# SX1262_e428v03a.net
KiCad netlist of a schematic drawn in Altium Designer
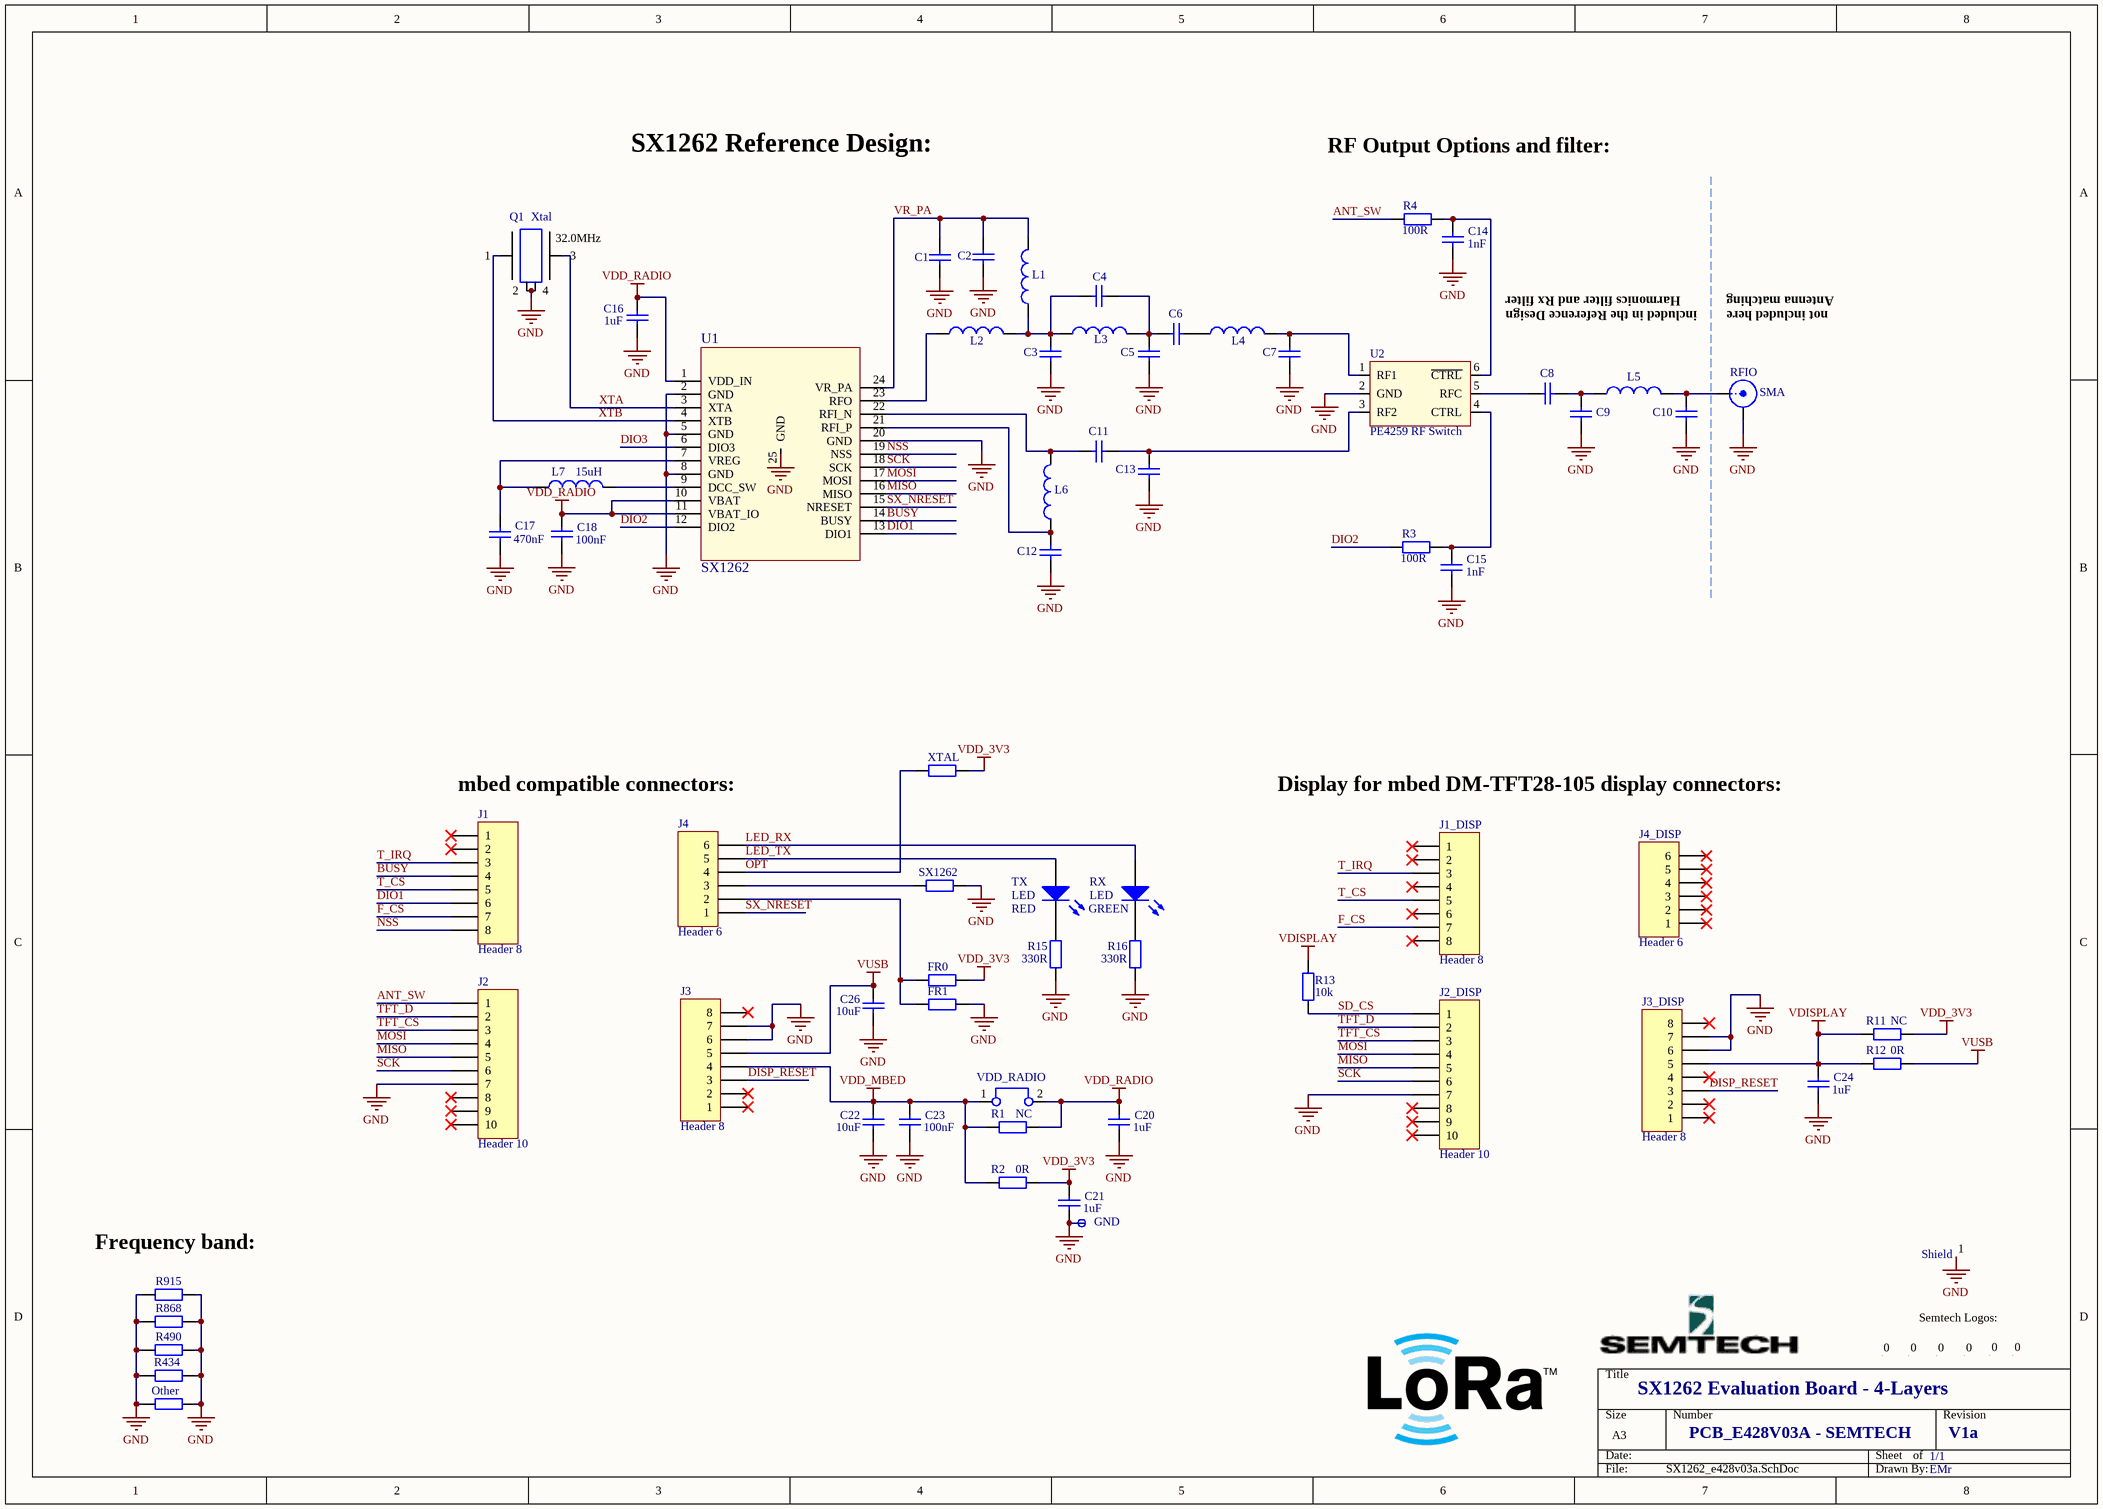
[diagram p0: SX1262_e428v03a.SchDoc]

(export (version "E")
  (design (tool "Eeschema 10.0.6"))
  (components
    (comp (ref "C1")
      (value "Cap")
      (footprint "rlc_402_smd")
      (description "Capacitor SMD")
      (fields (field (name "PUBLISHER") "Altium Limited"))
      (libsource (lib "SX1262_e428v03a") (part "Cap"))
    )
    (comp (ref "C2")
      (value "Cap")
      (footprint "rlc_402_smd")
      (description "Capacitor SMD")
      (fields (field (name "PUBLISHER") "Altium Limited"))
      (libsource (lib "SX1262_e428v03a") (part "Cap"))
    )
    (comp (ref "C3")
      (value "Cap")
      (footprint "rlc_402_smd")
      (description "Capacitor SMD")
      (fields (field (name "PUBLISHER") "Altium Limited"))
      (libsource (lib "SX1262_e428v03a") (part "Cap"))
    )
    (comp (ref "C4")
      (value "Cap")
      (footprint "rlc_402_smd")
      (description "Capacitor SMD")
      (fields (field (name "PUBLISHER") "Altium Limited"))
      (libsource (lib "SX1262_e428v03a") (part "Cap"))
    )
    (comp (ref "C5")
      (value "Cap")
      (footprint "rlc_402_smd")
      (description "Capacitor SMD")
      (fields (field (name "PUBLISHER") "Altium Limited"))
      (libsource (lib "SX1262_e428v03a") (part "Cap"))
    )
    (comp (ref "C6")
      (value "Cap")
      (footprint "rlc_402_smd")
      (description "Capacitor SMD")
      (fields (field (name "PUBLISHER") "Altium Limited"))
      (libsource (lib "SX1262_e428v03a") (part "Cap"))
    )
    (comp (ref "C7")
      (value "Cap")
      (footprint "rlc_402_smd")
      (description "Capacitor SMD")
      (fields (field (name "PUBLISHER") "Altium Limited"))
      (libsource (lib "SX1262_e428v03a") (part "Cap"))
    )
    (comp (ref "C8")
      (value "Cap")
      (footprint "rlc_402_smd")
      (description "Capacitor SMD")
      (fields (field (name "PUBLISHER") "Altium Limited"))
      (libsource (lib "SX1262_e428v03a") (part "Cap"))
    )
    (comp (ref "C9")
      (value "Cap")
      (footprint "rlc_402_smd")
      (description "Capacitor SMD")
      (fields (field (name "PUBLISHER") "Altium Limited"))
      (libsource (lib "SX1262_e428v03a") (part "Cap"))
    )
    (comp (ref "C10")
      (value "Cap")
      (footprint "rlc_402_smd")
      (description "Capacitor SMD")
      (fields (field (name "PUBLISHER") "Altium Limited"))
      (libsource (lib "SX1262_e428v03a") (part "Cap"))
    )
    (comp (ref "C11")
      (value "Cap")
      (footprint "rlc_402_smd")
      (description "Capacitor SMD")
      (fields (field (name "PUBLISHER") "Altium Limited"))
      (libsource (lib "SX1262_e428v03a") (part "Cap"))
    )
    (comp (ref "C12")
      (value "Cap")
      (footprint "rlc_402_smd")
      (description "Capacitor SMD")
      (fields (field (name "PUBLISHER") "Altium Limited"))
      (libsource (lib "SX1262_e428v03a") (part "Cap"))
    )
    (comp (ref "C13")
      (value "Cap")
      (footprint "rlc_402_smd")
      (description "Capacitor SMD")
      (fields (field (name "PUBLISHER") "Altium Limited"))
      (libsource (lib "SX1262_e428v03a") (part "Cap"))
    )
    (comp (ref "C14")
      (value "1nF")
      (footprint "rlc_402_smd")
      (description "Capacitor SMD")
      (fields (field (name "Comment") "Cap") (field (name "PUBLISHER") "Altium Limited"))
      (libsource (lib "SX1262_e428v03a") (part "Cap"))
    )
    (comp (ref "C15")
      (value "1nF")
      (footprint "rlc_402_smd")
      (description "Capacitor SMD")
      (fields (field (name "Comment") "Cap") (field (name "PUBLISHER") "Altium Limited"))
      (libsource (lib "SX1262_e428v03a") (part "Cap"))
    )
    (comp (ref "C16")
      (value "1uF")
      (footprint "rlc_402_smd")
      (description "Capacitor SMD")
      (fields (field (name "Comment") "Cap") (field (name "PUBLISHER") "Altium Limited"))
      (libsource (lib "SX1262_e428v03a") (part "Cap"))
    )
    (comp (ref "C17")
      (value "470nF")
      (footprint "rlc_402_smd")
      (description "Capacitor SMD")
      (fields (field (name "Comment") "Cap") (field (name "PUBLISHER") "Altium Limited"))
      (libsource (lib "SX1262_e428v03a") (part "Cap"))
    )
    (comp (ref "C18")
      (value "100nF")
      (footprint "rlc_402_smd")
      (description "Capacitor SMD")
      (fields (field (name "Comment") "Cap") (field (name "PUBLISHER") "Altium Limited"))
      (libsource (lib "SX1262_e428v03a") (part "Cap"))
    )
    (comp (ref "C20")
      (value "1uF")
      (footprint "rlc_603_smd")
      (description "Capacitor SMD")
      (fields (field (name "Comment") "Cap") (field (name "PUBLISHER") "Altium Limited"))
      (libsource (lib "SX1262_e428v03a") (part "Cap"))
    )
    (comp (ref "C21")
      (value "1uF")
      (footprint "rlc_603_smd")
      (description "Capacitor SMD")
      (fields (field (name "Comment") "Cap") (field (name "PUBLISHER") "Altium Limited"))
      (libsource (lib "SX1262_e428v03a") (part "Cap"))
    )
    (comp (ref "C22")
      (value "10uF")
      (footprint "rlc_805_smd")
      (description "Capacitor SMD")
      (fields (field (name "Comment") "Cap") (field (name "PUBLISHER") "Altium Limited"))
      (libsource (lib "SX1262_e428v03a") (part "Cap"))
    )
    (comp (ref "C23")
      (value "100nF")
      (footprint "rlc_402_smd")
      (description "Capacitor SMD")
      (fields (field (name "Comment") "Cap") (field (name "PUBLISHER") "Altium Limited"))
      (libsource (lib "SX1262_e428v03a") (part "Cap"))
    )
    (comp (ref "C24")
      (value "1uF")
      (footprint "rlc_402_smd")
      (description "Capacitor SMD")
      (fields (field (name "Comment") "Cap") (field (name "PUBLISHER") "Altium Limited"))
      (libsource (lib "SX1262_e428v03a") (part "Cap"))
    )
    (comp (ref "C26")
      (value "10uF")
      (footprint "rlc_805_smd")
      (description "Capacitor SMD")
      (fields (field (name "Comment") "Cap") (field (name "PUBLISHER") "Altium Limited"))
      (libsource (lib "SX1262_e428v03a") (part "Cap"))
    )
    (comp (ref "FR0")
      (value "Resistor")
      (footprint "rlc_402_smd")
      (description "Resistor SMD - IEC symbol version")
      (libsource (lib "") (part "Resistor_1"))
    )
    (comp (ref "FR1")
      (value "Resistor")
      (footprint "rlc_402_smd")
      (description "Resistor SMD - IEC symbol version")
      (libsource (lib "") (part "Resistor_1"))
    )
    (comp (ref "GND")
      (value "Test Pin")
      (footprint "pin_0.9mm")
      (libsource (lib "SX1262_e428v03a") (part "test_pin"))
    )
    (comp (ref "J1")
      (value "Header 8")
      (footprint "HDR1X8")
      (description "Header, 8-Pin")
      (fields (field (name "PUBLISHER") "Altium Limited"))
      (libsource (lib "SX1262_e428v03a") (part "Header 8"))
    )
    (comp (ref "J1_DISP")
      (value "Header 8")
      (footprint "HDR1X8")
      (description "Header, 8-Pin")
      (fields (field (name "PUBLISHER") "Altium Limited"))
      (libsource (lib "SX1262_e428v03a") (part "Header 8"))
    )
    (comp (ref "J2")
      (value "Header 10")
      (footprint "HDR1X10")
      (description "Header, 10-Pin")
      (fields (field (name "PUBLISHER") "Altium Limited"))
      (libsource (lib "SX1262_e428v03a") (part "Header 10"))
    )
    (comp (ref "J2_DISP")
      (value "Header 10")
      (footprint "HDR1X10")
      (description "Header, 10-Pin")
      (fields (field (name "PUBLISHER") "Altium Limited"))
      (libsource (lib "SX1262_e428v03a") (part "Header 10"))
    )
    (comp (ref "J3")
      (value "Header 8")
      (footprint "HDR1X8")
      (description "Header, 8-Pin")
      (fields (field (name "PUBLISHER") "Altium Limited"))
      (libsource (lib "") (part "Header 8_1"))
    )
    (comp (ref "J3_DISP")
      (value "Header 8")
      (footprint "HDR1X8")
      (description "Header, 8-Pin")
      (fields (field (name "PUBLISHER") "Altium Limited"))
      (libsource (lib "") (part "Header 8_1"))
    )
    (comp (ref "J4")
      (value "Header 6")
      (footprint "HDR1X6")
      (description "Header, 6-Pin")
      (fields (field (name "PUBLISHER") "Altium Limited"))
      (libsource (lib "SX1262_e428v03a") (part "Header 6"))
    )
    (comp (ref "J4_DISP")
      (value "Header 6")
      (footprint "HDR1X6")
      (description "Header, 6-Pin")
      (fields (field (name "PUBLISHER") "Altium Limited"))
      (libsource (lib "SX1262_e428v03a") (part "Header 6"))
    )
    (comp (ref "L1")
      (value "Inductor")
      (footprint "rlc_402_smd")
      (description "Inductor SMD")
      (fields (field (name "PUBLISHER") "Altium Limited"))
      (libsource (lib "SX1262_e428v03a") (part "Inductor"))
    )
    (comp (ref "L2")
      (value "Inductor")
      (footprint "rlc_402_smd")
      (description "Inductor SMD")
      (fields (field (name "PUBLISHER") "Altium Limited"))
      (libsource (lib "SX1262_e428v03a") (part "Inductor"))
    )
    (comp (ref "L3")
      (value "Inductor")
      (footprint "rlc_402_smd")
      (description "Inductor SMD")
      (fields (field (name "PUBLISHER") "Altium Limited"))
      (libsource (lib "SX1262_e428v03a") (part "Inductor"))
    )
    (comp (ref "L4")
      (value "Inductor")
      (footprint "rlc_402_smd")
      (description "Inductor SMD")
      (fields (field (name "PUBLISHER") "Altium Limited"))
      (libsource (lib "SX1262_e428v03a") (part "Inductor"))
    )
    (comp (ref "L5")
      (value "Inductor")
      (footprint "rlc_402_smd")
      (description "Inductor SMD")
      (fields (field (name "PUBLISHER") "Altium Limited"))
      (libsource (lib "SX1262_e428v03a") (part "Inductor"))
    )
    (comp (ref "L6")
      (value "Inductor")
      (footprint "rlc_402_smd")
      (description "Inductor SMD")
      (fields (field (name "PUBLISHER") "Altium Limited"))
      (libsource (lib "SX1262_e428v03a") (part "Inductor"))
    )
    (comp (ref "L7")
      (value "15uH")
      (footprint "rlc_805_smd enlarged")
      (description "Inductor SMD")
      (fields (field (name "Comment") "Inductor") (field (name "PUBLISHER") "Altium Limited"))
      (libsource (lib "SX1262_e428v03a") (part "Inductor"))
    )
    (comp (ref "Logo Bot")
      (value "Logo symbol")
      (footprint "logo_semtech_horiz_size4")
      (description "Schematic symbol for Logo")
      (libsource (lib "SX1262_e428v03a") (part "Logo"))
    )
    (comp (ref "Logo ESD")
      (value "Logo symbol")
      (footprint "Logo ESD")
      (description "Schematic symbol for Logo")
      (libsource (lib "SX1262_e428v03a") (part "Logo"))
    )
    (comp (ref "Logo Recycling1")
      (value "Logo symbol")
      (footprint "Logo Recycling1")
      (description "Schematic symbol for Logo")
      (libsource (lib "SX1262_e428v03a") (part "Logo"))
    )
    (comp (ref "Logo Semtech S")
      (value "Logo symbol")
      (footprint "logo_semtech_horiz_size3")
      (description "Schematic symbol for Logo")
      (libsource (lib "SX1262_e428v03a") (part "Logo"))
    )
    (comp (ref "Logo_LoRA1")
      (value "Logo symbol")
      (footprint "Logo LoRa Size4")
      (description "Schematic symbol for Logo")
      (libsource (lib "SX1262_e428v03a") (part "Logo"))
    )
    (comp (ref "Logo_LoRA2")
      (value "Logo symbol")
      (footprint "Logo LoRa Size3")
      (description "Schematic symbol for Logo")
      (libsource (lib "SX1262_e428v03a") (part "Logo"))
    )
    (comp (ref "Other")
      (value "Resistor")
      (footprint "rlc_402_smd")
      (description "Resistor SMD - IEC symbol version")
      (libsource (lib "SX1262_e428v03a") (part "Resistor"))
    )
    (comp (ref "Q1")
      (value "Xtal")
      (footprint "nd2016da")
      (description "Crystal with GND pins")
      (fields (field (name "ALTIUM_VALUE") "32.0MHz"))
      (libsource (lib "SX1262_e428v03a") (part "Xtal GND"))
    )
    (comp (ref "R1")
      (value "NC")
      (footprint "rlc_603_smd")
      (description "Resistor SMD - IEC symbol version")
      (fields (field (name "Comment") "Resistor"))
      (libsource (lib "SX1262_e428v03a") (part "Resistor"))
    )
    (comp (ref "R2")
      (value "0R")
      (footprint "rlc_603_smd")
      (description "Resistor SMD - IEC symbol version")
      (fields (field (name "Comment") "Resistor"))
      (libsource (lib "SX1262_e428v03a") (part "Resistor"))
    )
    (comp (ref "R3")
      (value "100R")
      (footprint "rlc_402_smd")
      (description "Resistor SMD - IEC symbol version")
      (fields (field (name "Comment") "Resistor"))
      (libsource (lib "SX1262_e428v03a") (part "Resistor"))
    )
    (comp (ref "R4")
      (value "100R")
      (footprint "rlc_402_smd")
      (description "Resistor SMD - IEC symbol version")
      (fields (field (name "Comment") "Resistor"))
      (libsource (lib "SX1262_e428v03a") (part "Resistor"))
    )
    (comp (ref "R11")
      (value "NC")
      (footprint "rlc_402_smd")
      (description "Resistor SMD - IEC symbol version")
      (fields (field (name "Comment") "Resistor"))
      (libsource (lib "SX1262_e428v03a") (part "Resistor"))
    )
    (comp (ref "R12")
      (value "0R")
      (footprint "rlc_402_smd")
      (description "Resistor SMD - IEC symbol version")
      (fields (field (name "Comment") "Resistor"))
      (libsource (lib "SX1262_e428v03a") (part "Resistor"))
    )
    (comp (ref "R13")
      (value "10k")
      (footprint "rlc_402_smd")
      (description "Resistor SMD - IEC symbol version")
      (fields (field (name "Comment") "Resistor"))
      (libsource (lib "SX1262_e428v03a") (part "Resistor"))
    )
    (comp (ref "R15")
      (value "330R")
      (footprint "rlc_402_smd")
      (description "Resistor SMD - IEC symbol version")
      (fields (field (name "Comment") "Resistor"))
      (libsource (lib "") (part "Resistor_2"))
    )
    (comp (ref "R16")
      (value "330R")
      (footprint "rlc_402_smd")
      (description "Resistor SMD - IEC symbol version")
      (fields (field (name "Comment") "Resistor"))
      (libsource (lib "") (part "Resistor_2"))
    )
    (comp (ref "R434")
      (value "Resistor")
      (footprint "rlc_402_smd")
      (description "Resistor SMD - IEC symbol version")
      (libsource (lib "SX1262_e428v03a") (part "Resistor"))
    )
    (comp (ref "R490")
      (value "Resistor")
      (footprint "rlc_402_smd")
      (description "Resistor SMD - IEC symbol version")
      (libsource (lib "SX1262_e428v03a") (part "Resistor"))
    )
    (comp (ref "R868")
      (value "Resistor")
      (footprint "rlc_402_smd")
      (description "Resistor SMD - IEC symbol version")
      (libsource (lib "SX1262_e428v03a") (part "Resistor"))
    )
    (comp (ref "R915")
      (value "Resistor")
      (footprint "rlc_402_smd")
      (description "Resistor SMD - IEC symbol version")
      (libsource (lib "SX1262_e428v03a") (part "Resistor"))
    )
    (comp (ref "RFIO")
      (value "SMA")
      (footprint "SMA_end_launch_1.0mm_9.52mm")
      (description "SMA Straight Connector")
      (fields (field (name "PUBLISHER") "Altium Limited"))
      (libsource (lib "SX1262_e428v03a") (part "SMA"))
    )
    (comp (ref "RX")
      (value "LED")
      (footprint "LGM676 LED")
      (fields (field (name "ALTIUM_VALUE") "GREEN"))
      (libsource (lib "SX1262_e428v03a") (part "LED"))
    )
    (comp (ref "Shield")
      (value "Logo symbol")
      (footprint "BMIS-209-F - Shield - Solder_Mask")
      (description "Shield - EMI Gasket - Standard Surface Mount Shields")
      (libsource (lib "SX1262_e428v03a") (part "Shield"))
    )
    (comp (ref "SX1262")
      (value "Resistor")
      (footprint "rlc_402_smd")
      (description "Resistor SMD - IEC symbol version")
      (libsource (lib "") (part "Resistor_1"))
    )
    (comp (ref "TX")
      (value "LED")
      (footprint "LGM676 LED")
      (fields (field (name "ALTIUM_VALUE") "RED"))
      (libsource (lib "SX1262_e428v03a") (part "LED"))
    )
    (comp (ref "U1")
      (value "SX1262")
      (footprint "vqfn24_4x4mm")
      (description "SX1262- Ultra low power RF transceiver")
      (libsource (lib "SX1262_e428v03a") (part "SX126x"))
    )
    (comp (ref "U2")
      (value "PE4259 RF Switch")
      (footprint "SC70-6")
      (description "PE4259 Peregrine RF Switch")
      (libsource (lib "SX1262_e428v03a") (part "PE4259 RF Switch"))
    )
    (comp (ref "VDD_RADIO")
      (value "Jumper")
      (footprint "bridge_254mm")
      (description "Jumper Wire")
      (libsource (lib "SX1262_e428v03a") (part "Jumper"))
    )
    (comp (ref "XTAL")
      (value "Resistor")
      (footprint "rlc_402_smd")
      (description "Resistor SMD - IEC symbol version")
      (libsource (lib "") (part "Resistor_1"))
    )
  )
  (nets
    (net (code "1") (name "/ANT_SW") (class "Default")
      (node (ref "J2") (pin "1") (pinfunction "1_1") (pintype "passive"))
      (node (ref "R4") (pin "2") (pinfunction "2_2") (pintype "passive"))
    )
    (net (code "2") (name "/BUSY") (class "Default")
      (node (ref "J1") (pin "4") (pinfunction "4_4") (pintype "passive"))
      (node (ref "U1") (pin "14") (pinfunction "BUSY_14") (pintype "passive"))
    )
    (net (code "3") (name "/DIO1") (class "Default")
      (node (ref "J1") (pin "6") (pinfunction "6_6") (pintype "passive"))
      (node (ref "U1") (pin "13") (pinfunction "DIO1_13") (pintype "passive"))
    )
    (net (code "4") (name "/DIO2") (class "Default")
      (node (ref "R3") (pin "2") (pinfunction "2_2") (pintype "passive"))
      (node (ref "U1") (pin "12") (pinfunction "DIO2_12") (pintype "passive"))
    )
    (net (code "5") (name "/DIO3") (class "Default")
      (node (ref "U1") (pin "6") (pinfunction "DIO3_6") (pintype "passive"))
    )
    (net (code "6") (name "/DISP_RESET") (class "Default")
      (node (ref "J3") (pin "3") (pinfunction "3_3") (pintype "passive"))
      (node (ref "J3_DISP") (pin "3") (pinfunction "3_3") (pintype "passive"))
    )
    (net (code "7") (name "/F_CS") (class "Default")
      (node (ref "J1") (pin "7") (pinfunction "7_7") (pintype "passive"))
      (node (ref "J1_DISP") (pin "7") (pinfunction "7_7") (pintype "passive"))
    )
    (net (code "8") (name "/LED_RX") (class "Default")
      (node (ref "J4") (pin "6") (pinfunction "6_6") (pintype "passive"))
      (node (ref "RX") (pin "1") (pinfunction "A_1") (pintype "passive"))
    )
    (net (code "9") (name "/LED_TX") (class "Default")
      (node (ref "J4") (pin "5") (pinfunction "5_5") (pintype "passive"))
      (node (ref "TX") (pin "1") (pinfunction "A_1") (pintype "passive"))
    )
    (net (code "10") (name "/MISO") (class "Default")
      (node (ref "J2") (pin "5") (pinfunction "5_5") (pintype "passive"))
      (node (ref "J2_DISP") (pin "5") (pinfunction "5_5") (pintype "passive"))
      (node (ref "U1") (pin "16") (pinfunction "MISO_16") (pintype "passive"))
    )
    (net (code "11") (name "/MOSI") (class "Default")
      (node (ref "J2") (pin "4") (pinfunction "4_4") (pintype "passive"))
      (node (ref "J2_DISP") (pin "4") (pinfunction "4_4") (pintype "passive"))
      (node (ref "U1") (pin "17") (pinfunction "MOSI_17") (pintype "passive"))
    )
    (net (code "12") (name "/NSS") (class "Default")
      (node (ref "J1") (pin "8") (pinfunction "8_8") (pintype "passive"))
      (node (ref "U1") (pin "19") (pinfunction "NSS_19") (pintype "passive"))
    )
    (net (code "13") (name "/OPT") (class "Default")
      (node (ref "J4") (pin "4") (pinfunction "4_4") (pintype "passive"))
      (node (ref "XTAL") (pin "2") (pinfunction "2_2") (pintype "passive"))
    )
    (net (code "14") (name "/SCK") (class "Default")
      (node (ref "J2") (pin "6") (pinfunction "6_6") (pintype "passive"))
      (node (ref "J2_DISP") (pin "6") (pinfunction "6_6") (pintype "passive"))
      (node (ref "U1") (pin "18") (pinfunction "SCK_18") (pintype "passive"))
    )
    (net (code "15") (name "/SD_CS") (class "Default")
      (node (ref "J2_DISP") (pin "1") (pinfunction "1_1") (pintype "passive"))
      (node (ref "R13") (pin "2") (pinfunction "2_2") (pintype "passive"))
    )
    (net (code "16") (name "/SX_NRESET") (class "Default")
      (node (ref "J4") (pin "1") (pinfunction "1_1") (pintype "passive"))
      (node (ref "U1") (pin "15") (pinfunction "NRESET_15") (pintype "passive"))
    )
    (net (code "17") (name "/TFT_CS") (class "Default")
      (node (ref "J2") (pin "3") (pinfunction "3_3") (pintype "passive"))
      (node (ref "J2_DISP") (pin "3") (pinfunction "3_3") (pintype "passive"))
    )
    (net (code "18") (name "/TFT_D") (class "Default")
      (node (ref "J2") (pin "2") (pinfunction "2_2") (pintype "passive"))
      (node (ref "J2_DISP") (pin "2") (pinfunction "2_2") (pintype "passive"))
    )
    (net (code "19") (name "/T_CS") (class "Default")
      (node (ref "J1") (pin "5") (pinfunction "5_5") (pintype "passive"))
      (node (ref "J1_DISP") (pin "5") (pinfunction "5_5") (pintype "passive"))
    )
    (net (code "20") (name "/T_IRQ") (class "Default")
      (node (ref "J1") (pin "3") (pinfunction "3_3") (pintype "passive"))
      (node (ref "J1_DISP") (pin "3") (pinfunction "3_3") (pintype "passive"))
    )
    (net (code "21") (name "/VR_PA") (class "Default")
      (node (ref "C1") (pin "2") (pinfunction "2_2") (pintype "passive"))
      (node (ref "C2") (pin "2") (pinfunction "2_2") (pintype "passive"))
      (node (ref "L1") (pin "2") (pinfunction "2_2") (pintype "passive"))
      (node (ref "U1") (pin "24") (pinfunction "VR_PA_24") (pintype "power_in"))
    )
    (net (code "22") (name "/XTA") (class "Default")
      (node (ref "Q1") (pin "3") (pinfunction "3_3") (pintype "passive"))
      (node (ref "U1") (pin "3") (pinfunction "XTA_3") (pintype "passive"))
    )
    (net (code "24") (name "/XTB") (class "Default")
      (node (ref "Q1") (pin "1") (pinfunction "1_1") (pintype "passive"))
      (node (ref "U1") (pin "4") (pinfunction "XTB_4") (pintype "passive"))
    )
    (net (code "25") (name "GND") (class "Default")
      (node (ref "C1") (pin "1") (pinfunction "1_1") (pintype "passive"))
      (node (ref "C10") (pin "1") (pinfunction "1_1") (pintype "passive"))
      (node (ref "C12") (pin "1") (pinfunction "1_1") (pintype "passive"))
      (node (ref "C13") (pin "1") (pinfunction "1_1") (pintype "passive"))
      (node (ref "C14") (pin "2") (pinfunction "2_2") (pintype "passive"))
      (node (ref "C15") (pin "2") (pinfunction "2_2") (pintype "passive"))
      (node (ref "C16") (pin "1") (pinfunction "1_1") (pintype "passive"))
      (node (ref "C17") (pin "1") (pinfunction "1_1") (pintype "passive"))
      (node (ref "C18") (pin "1") (pinfunction "1_1") (pintype "passive"))
      (node (ref "C2") (pin "1") (pinfunction "1_1") (pintype "passive"))
      (node (ref "C20") (pin "1") (pinfunction "1_1") (pintype "passive"))
      (node (ref "C21") (pin "1") (pinfunction "1_1") (pintype "passive"))
      (node (ref "C22") (pin "1") (pinfunction "1_1") (pintype "passive"))
      (node (ref "C23") (pin "1") (pinfunction "1_1") (pintype "passive"))
      (node (ref "C24") (pin "1") (pinfunction "1_1") (pintype "passive"))
      (node (ref "C26") (pin "1") (pinfunction "1_1") (pintype "passive"))
      (node (ref "C3") (pin "1") (pinfunction "1_1") (pintype "passive"))
      (node (ref "C5") (pin "1") (pinfunction "1_1") (pintype "passive"))
      (node (ref "C7") (pin "1") (pinfunction "1_1") (pintype "passive"))
      (node (ref "C9") (pin "1") (pinfunction "1_1") (pintype "passive"))
      (node (ref "FR1") (pin "1") (pinfunction "1_1") (pintype "passive"))
      (node (ref "GND") (pin "1") (pinfunction "pin_1") (pintype "passive"))
      (node (ref "J2") (pin "7") (pinfunction "7_7") (pintype "passive"))
      (node (ref "J2_DISP") (pin "7") (pinfunction "7_7") (pintype "passive"))
      (node (ref "J3") (pin "6") (pinfunction "6_6") (pintype "passive"))
      (node (ref "J3") (pin "7") (pinfunction "7_7") (pintype "passive"))
      (node (ref "J3_DISP") (pin "6") (pinfunction "6_6") (pintype "passive"))
      (node (ref "J3_DISP") (pin "7") (pinfunction "7_7") (pintype "passive"))
      (node (ref "Other") (pin "1") (pinfunction "1_1") (pintype "passive"))
      (node (ref "Other") (pin "2") (pinfunction "2_2") (pintype "passive"))
      (node (ref "Q1") (pin "2") (pinfunction "2_2") (pintype "passive"))
      (node (ref "Q1") (pin "4") (pinfunction "4_4") (pintype "passive"))
      (node (ref "R15") (pin "1") (pinfunction "1_1") (pintype "passive"))
      (node (ref "R16") (pin "1") (pinfunction "1_1") (pintype "passive"))
      (node (ref "R434") (pin "1") (pinfunction "1_1") (pintype "passive"))
      (node (ref "R434") (pin "2") (pinfunction "2_2") (pintype "passive"))
      (node (ref "R490") (pin "1") (pinfunction "1_1") (pintype "passive"))
      (node (ref "R490") (pin "2") (pinfunction "2_2") (pintype "passive"))
      (node (ref "R868") (pin "1") (pinfunction "1_1") (pintype "passive"))
      (node (ref "R868") (pin "2") (pinfunction "2_2") (pintype "passive"))
      (node (ref "R915") (pin "1") (pinfunction "1_1") (pintype "passive"))
      (node (ref "R915") (pin "2") (pinfunction "2_2") (pintype "passive"))
      (node (ref "RFIO") (pin "2") (pinfunction "GND_2") (pintype "passive"))
      (node (ref "SX1262") (pin "1") (pinfunction "1_1") (pintype "passive"))
      (node (ref "Shield") (pin "1") (pinfunction "1_1") (pintype "passive"))
      (node (ref "U1") (pin "2") (pinfunction "GND_2") (pintype "passive"))
      (node (ref "U1") (pin "20") (pinfunction "GND_20") (pintype "passive"))
      (node (ref "U1") (pin "25") (pinfunction "GND_25") (pintype "passive"))
      (node (ref "U1") (pin "5") (pinfunction "GND_5") (pintype "passive"))
      (node (ref "U1") (pin "8") (pinfunction "GND_8") (pintype "passive"))
      (node (ref "U2") (pin "2") (pinfunction "GND_2") (pintype "passive"))
    )
    (net (code "26") (name "Net-(C3-Pad2)") (class "Default")
      (node (ref "C3") (pin "2") (pinfunction "2_2") (pintype "passive"))
      (node (ref "C4") (pin "2") (pinfunction "2_2") (pintype "passive"))
      (node (ref "L1") (pin "1") (pinfunction "1_1") (pintype "passive"))
      (node (ref "L2") (pin "2") (pinfunction "2_2") (pintype "passive"))
      (node (ref "L3") (pin "1") (pinfunction "1_1") (pintype "passive"))
    )
    (net (code "27") (name "Net-(C4-Pad1)") (class "Default")
      (node (ref "C4") (pin "1") (pinfunction "1_1") (pintype "passive"))
      (node (ref "C5") (pin "2") (pinfunction "2_2") (pintype "passive"))
      (node (ref "C6") (pin "2") (pinfunction "2_2") (pintype "passive"))
      (node (ref "L3") (pin "2") (pinfunction "2_2") (pintype "passive"))
    )
    (net (code "28") (name "Net-(C6-Pad1)") (class "Default")
      (node (ref "C6") (pin "1") (pinfunction "1_1") (pintype "passive"))
      (node (ref "L4") (pin "1") (pinfunction "1_1") (pintype "passive"))
    )
    (net (code "29") (name "Net-(C8-Pad1)") (class "Default")
      (node (ref "C8") (pin "1") (pinfunction "1_1") (pintype "passive"))
      (node (ref "C9") (pin "2") (pinfunction "2_2") (pintype "passive"))
      (node (ref "L5") (pin "1") (pinfunction "1_1") (pintype "passive"))
    )
    (net (code "30") (name "Net-(FR0-Pad2)") (class "Default")
      (node (ref "FR0") (pin "2") (pinfunction "2_2") (pintype "passive"))
      (node (ref "FR1") (pin "2") (pinfunction "2_2") (pintype "passive"))
      (node (ref "J4") (pin "2") (pinfunction "2_2") (pintype "passive"))
    )
    (net (code "31") (name "Net-(J4-Pad3)") (class "Default")
      (node (ref "J4") (pin "3") (pinfunction "3_3") (pintype "passive"))
      (node (ref "SX1262") (pin "2") (pinfunction "2_2") (pintype "passive"))
    )
    (net (code "32") (name "Net-(RFIO-Signal)") (class "Default")
      (node (ref "C10") (pin "2") (pinfunction "2_2") (pintype "passive"))
      (node (ref "L5") (pin "2") (pinfunction "2_2") (pintype "passive"))
      (node (ref "RFIO") (pin "1") (pinfunction "Signal_1") (pintype "passive"))
    )
    (net (code "33") (name "Net-(RX-K)") (class "Default")
      (node (ref "R16") (pin "2") (pinfunction "2_2") (pintype "passive"))
      (node (ref "RX") (pin "2") (pinfunction "K_2") (pintype "passive"))
    )
    (net (code "34") (name "Net-(TX-K)") (class "Default")
      (node (ref "R15") (pin "2") (pinfunction "2_2") (pintype "passive"))
      (node (ref "TX") (pin "2") (pinfunction "K_2") (pintype "passive"))
    )
    (net (code "35") (name "Net-(U1-DCC_SW)") (class "Default")
      (node (ref "L7") (pin "2") (pinfunction "2_2") (pintype "passive"))
      (node (ref "U1") (pin "9") (pinfunction "DCC_SW_9") (pintype "power_in"))
    )
    (net (code "36") (name "Net-(U1-RFI_N)") (class "Default")
      (node (ref "C11") (pin "2") (pinfunction "2_2") (pintype "passive"))
      (node (ref "L6") (pin "2") (pinfunction "2_2") (pintype "passive"))
      (node (ref "U1") (pin "22") (pinfunction "RFI_N_22") (pintype "passive"))
    )
    (net (code "37") (name "Net-(U1-RFI_P)") (class "Default")
      (node (ref "C12") (pin "2") (pinfunction "2_2") (pintype "passive"))
      (node (ref "L6") (pin "1") (pinfunction "1_1") (pintype "passive"))
      (node (ref "U1") (pin "21") (pinfunction "RFI_P_21") (pintype "passive"))
    )
    (net (code "38") (name "Net-(U1-RFO)") (class "Default")
      (node (ref "L2") (pin "1") (pinfunction "1_1") (pintype "passive"))
      (node (ref "U1") (pin "23") (pinfunction "RFO_23") (pintype "passive"))
    )
    (net (code "39") (name "Net-(U1-VREG)") (class "Default")
      (node (ref "C17") (pin "2") (pinfunction "2_2") (pintype "passive"))
      (node (ref "L7") (pin "1") (pinfunction "1_1") (pintype "passive"))
      (node (ref "U1") (pin "7") (pinfunction "VREG_7") (pintype "power_in"))
    )
    (net (code "40") (name "Net-(U2-CTRL)") (class "Default")
      (node (ref "C15") (pin "1") (pinfunction "1_1") (pintype "passive"))
      (node (ref "R3") (pin "1") (pinfunction "1_1") (pintype "passive"))
      (node (ref "U2") (pin "4") (pinfunction "CTRL_4") (pintype "passive"))
    )
    (net (code "41") (name "Net-(U2-RF1)") (class "Default")
      (node (ref "C7") (pin "2") (pinfunction "2_2") (pintype "passive"))
      (node (ref "L4") (pin "2") (pinfunction "2_2") (pintype "passive"))
      (node (ref "U2") (pin "1") (pinfunction "RF1_1") (pintype "passive"))
    )
    (net (code "42") (name "Net-(U2-RF2)") (class "Default")
      (node (ref "C11") (pin "1") (pinfunction "1_1") (pintype "passive"))
      (node (ref "C13") (pin "2") (pinfunction "2_2") (pintype "passive"))
      (node (ref "U2") (pin "3") (pinfunction "RF2_3") (pintype "passive"))
    )
    (net (code "43") (name "Net-(U2-RFC)") (class "Default")
      (node (ref "C8") (pin "2") (pinfunction "2_2") (pintype "passive"))
      (node (ref "U2") (pin "5") (pinfunction "RFC_5") (pintype "passive"))
    )
    (net (code "44") (name "Net-(U2-~{CTRL})") (class "Default")
      (node (ref "C14") (pin "1") (pinfunction "1_1") (pintype "passive"))
      (node (ref "R4") (pin "1") (pinfunction "1_1") (pintype "passive"))
      (node (ref "U2") (pin "6") (pinfunction "~{CTRL}_6") (pintype "passive"))
    )
    (net (code "45") (name "VDD_3V3") (class "Default")
      (node (ref "C21") (pin "2") (pinfunction "2_2") (pintype "passive"))
      (node (ref "FR0") (pin "1") (pinfunction "1_1") (pintype "passive"))
      (node (ref "R11") (pin "1") (pinfunction "1_1") (pintype "passive"))
      (node (ref "R2") (pin "1") (pinfunction "1_1") (pintype "passive"))
      (node (ref "XTAL") (pin "1") (pinfunction "1_1") (pintype "passive"))
    )
    (net (code "46") (name "VDD_MBED") (class "Default")
      (node (ref "C22") (pin "2") (pinfunction "2_2") (pintype "passive"))
      (node (ref "C23") (pin "2") (pinfunction "2_2") (pintype "passive"))
      (node (ref "J3") (pin "4") (pinfunction "4_4") (pintype "passive"))
      (node (ref "R1") (pin "2") (pinfunction "2_2") (pintype "passive"))
      (node (ref "R2") (pin "2") (pinfunction "2_2") (pintype "passive"))
      (node (ref "VDD_RADIO") (pin "1") (pinfunction "1_1") (pintype "passive"))
    )
    (net (code "47") (name "VDD_RADIO") (class "Default")
      (node (ref "C16") (pin "2") (pinfunction "2_2") (pintype "passive"))
      (node (ref "C18") (pin "2") (pinfunction "2_2") (pintype "passive"))
      (node (ref "C20") (pin "2") (pinfunction "2_2") (pintype "passive"))
      (node (ref "R1") (pin "1") (pinfunction "1_1") (pintype "passive"))
      (node (ref "U1") (pin "1") (pinfunction "VDD_IN_1") (pintype "power_in"))
      (node (ref "U1") (pin "10") (pinfunction "VBAT_10") (pintype "power_in"))
      (node (ref "U1") (pin "11") (pinfunction "VBAT_IO_11") (pintype "power_in"))
      (node (ref "VDD_RADIO") (pin "2") (pinfunction "2_2") (pintype "passive"))
    )
    (net (code "48") (name "VDISPLAY") (class "Default")
      (node (ref "C24") (pin "2") (pinfunction "2_2") (pintype "passive"))
      (node (ref "J3_DISP") (pin "5") (pinfunction "5_5") (pintype "passive"))
      (node (ref "R11") (pin "2") (pinfunction "2_2") (pintype "passive"))
      (node (ref "R12") (pin "2") (pinfunction "2_2") (pintype "passive"))
      (node (ref "R13") (pin "1") (pinfunction "1_1") (pintype "passive"))
    )
    (net (code "49") (name "VUSB") (class "Default")
      (node (ref "C26") (pin "2") (pinfunction "2_2") (pintype "passive"))
      (node (ref "J3") (pin "5") (pinfunction "5_5") (pintype "passive"))
      (node (ref "R12") (pin "1") (pinfunction "1_1") (pintype "passive"))
    )
    (net (code "50") (name "unconnected-(J1-Pad1)") (class "Default")
      (node (ref "J1") (pin "1") (pinfunction "1_1") (pintype "passive+no_connect"))
    )
    (net (code "51") (name "unconnected-(J1-Pad2)") (class "Default")
      (node (ref "J1") (pin "2") (pinfunction "2_2") (pintype "passive+no_connect"))
    )
    (net (code "52") (name "unconnected-(J1_DISP-Pad1)") (class "Default")
      (node (ref "J1_DISP") (pin "1") (pinfunction "1_1") (pintype "passive+no_connect"))
    )
    (net (code "53") (name "unconnected-(J1_DISP-Pad2)") (class "Default")
      (node (ref "J1_DISP") (pin "2") (pinfunction "2_2") (pintype "passive+no_connect"))
    )
    (net (code "54") (name "unconnected-(J1_DISP-Pad4)") (class "Default")
      (node (ref "J1_DISP") (pin "4") (pinfunction "4_4") (pintype "passive+no_connect"))
    )
    (net (code "55") (name "unconnected-(J1_DISP-Pad6)") (class "Default")
      (node (ref "J1_DISP") (pin "6") (pinfunction "6_6") (pintype "passive+no_connect"))
    )
    (net (code "56") (name "unconnected-(J1_DISP-Pad8)") (class "Default")
      (node (ref "J1_DISP") (pin "8") (pinfunction "8_8") (pintype "passive+no_connect"))
    )
    (net (code "57") (name "unconnected-(J2-Pad8)") (class "Default")
      (node (ref "J2") (pin "8") (pinfunction "8_8") (pintype "passive+no_connect"))
    )
    (net (code "58") (name "unconnected-(J2-Pad9)") (class "Default")
      (node (ref "J2") (pin "9") (pinfunction "9_9") (pintype "passive+no_connect"))
    )
    (net (code "59") (name "unconnected-(J2-Pad10)") (class "Default")
      (node (ref "J2") (pin "10") (pinfunction "10_10") (pintype "passive+no_connect"))
    )
    (net (code "60") (name "unconnected-(J2_DISP-Pad8)") (class "Default")
      (node (ref "J2_DISP") (pin "8") (pinfunction "8_8") (pintype "passive+no_connect"))
    )
    (net (code "61") (name "unconnected-(J2_DISP-Pad9)") (class "Default")
      (node (ref "J2_DISP") (pin "9") (pinfunction "9_9") (pintype "passive+no_connect"))
    )
    (net (code "62") (name "unconnected-(J2_DISP-Pad10)") (class "Default")
      (node (ref "J2_DISP") (pin "10") (pinfunction "10_10") (pintype "passive+no_connect"))
    )
    (net (code "63") (name "unconnected-(J3-Pad1)") (class "Default")
      (node (ref "J3") (pin "1") (pinfunction "1_1") (pintype "passive+no_connect"))
    )
    (net (code "64") (name "unconnected-(J3-Pad2)") (class "Default")
      (node (ref "J3") (pin "2") (pinfunction "2_2") (pintype "passive+no_connect"))
    )
    (net (code "65") (name "unconnected-(J3-Pad8)") (class "Default")
      (node (ref "J3") (pin "8") (pinfunction "8_8") (pintype "passive+no_connect"))
    )
    (net (code "66") (name "unconnected-(J3_DISP-Pad1)") (class "Default")
      (node (ref "J3_DISP") (pin "1") (pinfunction "1_1") (pintype "passive+no_connect"))
    )
    (net (code "67") (name "unconnected-(J3_DISP-Pad2)") (class "Default")
      (node (ref "J3_DISP") (pin "2") (pinfunction "2_2") (pintype "passive+no_connect"))
    )
    (net (code "68") (name "unconnected-(J3_DISP-Pad4)") (class "Default")
      (node (ref "J3_DISP") (pin "4") (pinfunction "4_4") (pintype "passive+no_connect"))
    )
    (net (code "69") (name "unconnected-(J3_DISP-Pad8)") (class "Default")
      (node (ref "J3_DISP") (pin "8") (pinfunction "8_8") (pintype "passive+no_connect"))
    )
    (net (code "70") (name "unconnected-(J4_DISP-Pad1)") (class "Default")
      (node (ref "J4_DISP") (pin "1") (pinfunction "1_1") (pintype "passive+no_connect"))
    )
    (net (code "71") (name "unconnected-(J4_DISP-Pad2)") (class "Default")
      (node (ref "J4_DISP") (pin "2") (pinfunction "2_2") (pintype "passive+no_connect"))
    )
    (net (code "72") (name "unconnected-(J4_DISP-Pad3)") (class "Default")
      (node (ref "J4_DISP") (pin "3") (pinfunction "3_3") (pintype "passive+no_connect"))
    )
    (net (code "73") (name "unconnected-(J4_DISP-Pad4)") (class "Default")
      (node (ref "J4_DISP") (pin "4") (pinfunction "4_4") (pintype "passive+no_connect"))
    )
    (net (code "74") (name "unconnected-(J4_DISP-Pad5)") (class "Default")
      (node (ref "J4_DISP") (pin "5") (pinfunction "5_5") (pintype "passive+no_connect"))
    )
    (net (code "75") (name "unconnected-(J4_DISP-Pad6)") (class "Default")
      (node (ref "J4_DISP") (pin "6") (pinfunction "6_6") (pintype "passive+no_connect"))
    )
    (net (code "76") (name "unconnected-(Logo Bot-Pad0)") (class "Default")
      (node (ref "Logo Bot") (pin "0") (pinfunction "0_0") (pintype "passive"))
    )
    (net (code "77") (name "unconnected-(Logo ESD-Pad0)") (class "Default")
      (node (ref "Logo ESD") (pin "0") (pinfunction "0_0") (pintype "passive"))
    )
    (net (code "78") (name "unconnected-(Logo Recycling1-Pad0)") (class "Default")
      (node (ref "Logo Recycling1") (pin "0") (pinfunction "0_0") (pintype "passive"))
    )
    (net (code "79") (name "unconnected-(Logo Semtech S-Pad0)") (class "Default")
      (node (ref "Logo Semtech S") (pin "0") (pinfunction "0_0") (pintype "passive"))
    )
    (net (code "80") (name "unconnected-(Logo_LoRA1-Pad0)") (class "Default")
      (node (ref "Logo_LoRA1") (pin "0") (pinfunction "0_0") (pintype "passive"))
    )
    (net (code "81") (name "unconnected-(Logo_LoRA2-Pad0)") (class "Default")
      (node (ref "Logo_LoRA2") (pin "0") (pinfunction "0_0") (pintype "passive"))
    )
  )
)
